# MCU.net
KiCad netlist of a schematic drawn in Altium Designer
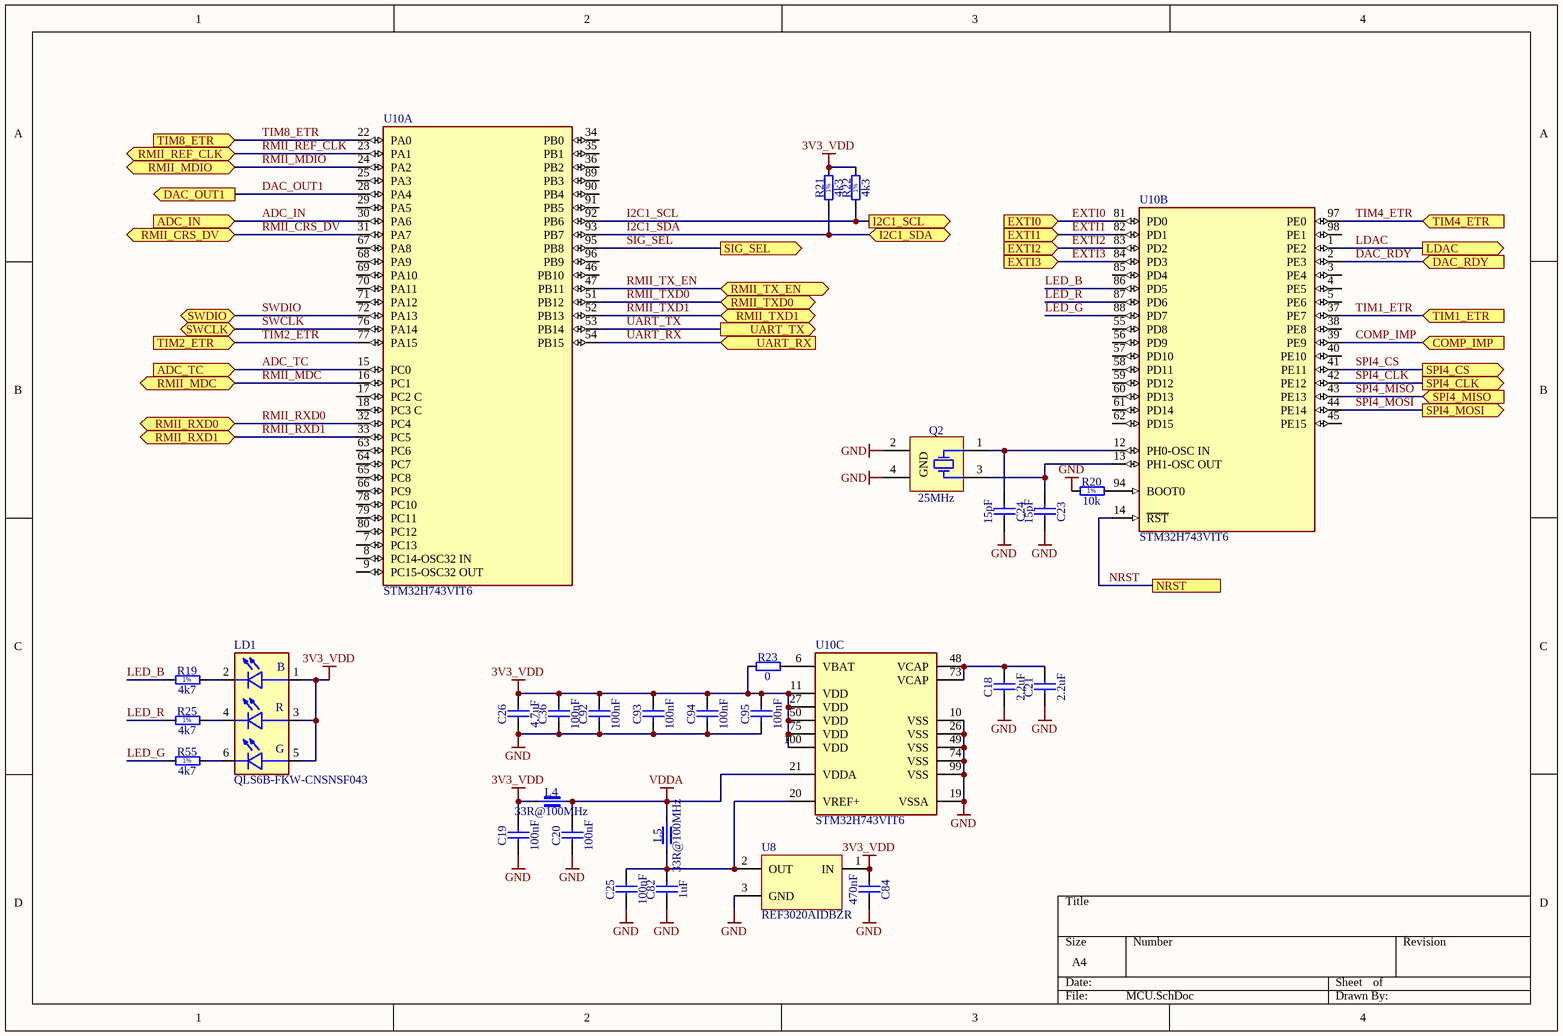
[diagram p0: MCU.SchDoc]

(export (version "E")
  (design (tool "Eeschema 10.0.6"))
  (components
    (comp (ref "C18")
      (value "2.2uF")
      (footprint "CAPC1608X87N")
      (description "Non-polarised capacitor")
      (fields
        (field (name "PART NUMBER") "CC0603_2.2UF_16V_10%_X5R")
        (field (name "VOLTAGE") "16V")
        (field (name "AUTHOR") "CERN DEM JLC")
      )
      (libsource (lib "Capacitors") (part "Capacitor - non polarized"))
    )
    (comp (ref "C19")
      (value "100nF")
      (footprint "CAPC1005X55N")
      (description "Non-polarised capacitor")
      (fields
        (field (name "PART NUMBER") "CC0402_100NF_16V_10%_X7R")
        (field (name "VOLTAGE") "16V")
        (field (name "AUTHOR") "CERN DEM JLC")
      )
      (libsource (lib "Capacitors") (part "Capacitor - non polarized"))
    )
    (comp (ref "C20")
      (value "100nF")
      (footprint "CAPC1005X55N")
      (description "Non-polarised capacitor")
      (fields
        (field (name "PART NUMBER") "CC0402_100NF_16V_10%_X7R")
        (field (name "VOLTAGE") "16V")
        (field (name "AUTHOR") "CERN DEM JLC")
      )
      (libsource (lib "Capacitors") (part "Capacitor - non polarized"))
    )
    (comp (ref "C21")
      (value "2.2uF")
      (footprint "CAPC1608X87N")
      (description "Non-polarised capacitor")
      (fields
        (field (name "PART NUMBER") "CC0603_2.2UF_16V_10%_X5R")
        (field (name "VOLTAGE") "16V")
        (field (name "AUTHOR") "CERN DEM JLC")
      )
      (libsource (lib "Capacitors") (part "Capacitor - non polarized"))
    )
    (comp (ref "C23")
      (value "15pF")
      (footprint "CAPC1005X55N")
      (description "Non-polarised capacitor")
      (fields
        (field (name "PART NUMBER") "CC0402_15PF_50V_5%_C0G")
        (field (name "VOLTAGE") "50V")
        (field (name "AUTHOR") "CERN DEM JLC")
      )
      (libsource (lib "Capacitors") (part "Capacitor - non polarized"))
    )
    (comp (ref "C24")
      (value "15pF")
      (footprint "CAPC1005X55N")
      (description "Non-polarised capacitor")
      (fields
        (field (name "PART NUMBER") "CC0402_15PF_50V_5%_C0G")
        (field (name "VOLTAGE") "50V")
        (field (name "AUTHOR") "CERN DEM JLC")
      )
      (libsource (lib "Capacitors") (part "Capacitor - non polarized"))
    )
    (comp (ref "C25")
      (value "100nF")
      (footprint "CAPC1005X55N")
      (description "Non-polarised capacitor")
      (fields
        (field (name "PART NUMBER") "CC0402_100NF_16V_10%_X7R")
        (field (name "VOLTAGE") "16V")
        (field (name "AUTHOR") "CERN DEM JLC")
      )
      (libsource (lib "Capacitors") (part "Capacitor - non polarized"))
    )
    (comp (ref "C26")
      (value "4.7uF")
      (footprint "CAPC1709X95N")
      (description "Non-polarised capacitor")
      (fields
        (field (name "PART NUMBER") "CC0603_4.7UF_16V_10%_X5R")
        (field (name "VOLTAGE") "16V")
        (field (name "AUTHOR") "CERN DEM JLC")
      )
      (libsource (lib "Capacitors") (part "Capacitor - non polarized"))
    )
    (comp (ref "C36")
      (value "100nF")
      (footprint "CAPC1005X55N")
      (description "Non-polarised capacitor")
      (fields
        (field (name "PART NUMBER") "CC0402_100NF_16V_10%_X7R")
        (field (name "VOLTAGE") "16V")
        (field (name "AUTHOR") "CERN DEM JLC")
      )
      (libsource (lib "Capacitors") (part "Capacitor - non polarized"))
    )
    (comp (ref "C82")
      (value "1uF")
      (footprint "CAPC1005X55N")
      (description "Non-polarised capacitor")
      (fields
        (field (name "PART NUMBER") "CC0402_1UF_16V_10%_X5R")
        (field (name "VOLTAGE") "16V")
        (field (name "AUTHOR") "CERN DEM JLC")
      )
      (libsource (lib "Capacitors") (part "Capacitor - non polarized"))
    )
    (comp (ref "C84")
      (value "470nF")
      (footprint "CAPC1005X55N")
      (description "Non-polarised capacitor")
      (fields
        (field (name "PART NUMBER") "CC0402_470NF_16V_10%_X5R")
        (field (name "VOLTAGE") "16V")
        (field (name "AUTHOR") "CERN DEM JLC")
      )
      (libsource (lib "Capacitors") (part "Capacitor - non polarized"))
    )
    (comp (ref "C92")
      (value "100nF")
      (footprint "CAPC1005X55N")
      (description "Non-polarised capacitor")
      (fields
        (field (name "PART NUMBER") "CC0402_100NF_16V_10%_X7R")
        (field (name "VOLTAGE") "16V")
        (field (name "AUTHOR") "CERN DEM JLC")
      )
      (libsource (lib "Capacitors") (part "Capacitor - non polarized"))
    )
    (comp (ref "C93")
      (value "100nF")
      (footprint "CAPC1005X55N")
      (description "Non-polarised capacitor")
      (fields
        (field (name "PART NUMBER") "CC0402_100NF_16V_10%_X7R")
        (field (name "VOLTAGE") "16V")
        (field (name "AUTHOR") "CERN DEM JLC")
      )
      (libsource (lib "Capacitors") (part "Capacitor - non polarized"))
    )
    (comp (ref "C94")
      (value "100nF")
      (footprint "CAPC1005X55N")
      (description "Non-polarised capacitor")
      (fields
        (field (name "PART NUMBER") "CC0402_100NF_16V_10%_X7R")
        (field (name "VOLTAGE") "16V")
        (field (name "AUTHOR") "CERN DEM JLC")
      )
      (libsource (lib "Capacitors") (part "Capacitor - non polarized"))
    )
    (comp (ref "C95")
      (value "100nF")
      (footprint "CAPC1005X55N")
      (description "Non-polarised capacitor")
      (fields
        (field (name "PART NUMBER") "CC0402_100NF_16V_10%_X7R")
        (field (name "VOLTAGE") "16V")
        (field (name "AUTHOR") "CERN DEM JLC")
      )
      (libsource (lib "Capacitors") (part "Capacitor - non polarized"))
    )
    (comp (ref "L4")
      (value "33R@100MHz")
      (footprint "INDC1005X55N")
      (fields
        (field (name "PART NUMBER") "IND0402_MURATA_BLM15PX330SN1D")
        (field (name "POWER") "3A")
        (field (name "TOLERANCE") "±25%")
        (field (name "AUTHOR") "CERN DEM JMW")
      )
      (libsource (lib "") (part "Ferrite Bead_1"))
    )
    (comp (ref "L5")
      (value "33R@100MHz")
      (footprint "INDC1005X55N")
      (fields
        (field (name "PART NUMBER") "IND0402_MURATA_BLM15PX330SN1D")
        (field (name "POWER") "3A")
        (field (name "TOLERANCE") "±25%")
        (field (name "AUTHOR") "CERN DEM JMW")
      )
      (libsource (lib "Inductors & Transformers") (part "Ferrite Bead"))
    )
    (comp (ref "LD1")
      (value "QLS6B-FKW-CNSNSF043")
      (footprint "LED_QLS6B-FKW-CNSNSF043")
      (fields (field (name "MF") "Cree Inc."))
      (libsource (lib "QLS6B-FKW-CNSNSF043") (part "QLS6B-FKW-CNSNSF043"))
    )
    (comp (ref "Q2")
      (value "25MHz")
      (footprint "XTAL_EPSON_TSX-3225")
      (description "Crystal 4 pins 1=XTAL Control 2=GND3=XTAL 4=GND")
      (fields
        (field (name "PART NUMBER") "XTAL_25MHZ_EPSON_TSX-3225 25.0000MF10Z-AC")
        (field (name "MANUFACTURER") "EPSON")
        (field (name "AUTHOR") "CERN DEM JLC")
      )
      (libsource (lib "ICs And Semiconductors") (part "Quartz Crystal 1X 2GND 3X 4GND"))
    )
    (comp (ref "R19")
      (value "4k7")
      (footprint "RESC1005X40N")
      (description "Resistor - 1%")
      (fields
        (field (name "PART NUMBER") "R0402_4K7_1%_0.0625W_100PPM")
        (field (name "POWER") "0.0625W")
        (field (name "AUTHOR") "CERN DEM JLC")
      )
      (libsource (lib "Resistors") (part "Resistor - 1%"))
    )
    (comp (ref "R20")
      (value "10k")
      (footprint "RESC1005X40N")
      (description "Resistor - 1%")
      (fields
        (field (name "PART NUMBER") "R0402_10K_1%_0.0625W_100PPM")
        (field (name "POWER") "0.0625W")
        (field (name "AUTHOR") "CERN DEM JLC")
      )
      (libsource (lib "Resistors") (part "Resistor - 1%"))
    )
    (comp (ref "R21")
      (value "4k3")
      (footprint "RESC1005X40N")
      (description "Resistor - 1%")
      (fields
        (field (name "PART NUMBER") "R0402_4K3_1%_0.0625W_100PPM")
        (field (name "POWER") "0.0625W")
        (field (name "AUTHOR") "CERN DEM JLC")
      )
      (libsource (lib "Resistors") (part "Resistor - 1%"))
    )
    (comp (ref "R22")
      (value "4k3")
      (footprint "RESC1005X40N")
      (description "Resistor - 1%")
      (fields
        (field (name "PART NUMBER") "R0402_4K3_1%_0.0625W_100PPM")
        (field (name "POWER") "0.0625W")
        (field (name "AUTHOR") "CERN DEM JLC")
      )
      (libsource (lib "Resistors") (part "Resistor - 1%"))
    )
    (comp (ref "R23")
      (value "0")
      (footprint "RESC1005X40N")
      (description "Resistor")
      (fields
        (field (name "PART NUMBER") "R0402_0R_JUMPER")
        (field (name "MANUFACTURER") "GENERIC")
        (field (name "AUTHOR") "CERN DEM JLC")
      )
      (libsource (lib "Resistors") (part "Resistor"))
    )
    (comp (ref "R25")
      (value "4k7")
      (footprint "RESC1005X40N")
      (description "Resistor - 1%")
      (fields
        (field (name "PART NUMBER") "R0402_4K7_1%_0.0625W_100PPM")
        (field (name "POWER") "0.0625W")
        (field (name "AUTHOR") "CERN DEM JLC")
      )
      (libsource (lib "Resistors") (part "Resistor - 1%"))
    )
    (comp (ref "R55")
      (value "4k7")
      (footprint "RESC1005X40N")
      (description "Resistor - 1%")
      (fields
        (field (name "PART NUMBER") "R0402_4K7_1%_0.0625W_100PPM")
        (field (name "POWER") "0.0625W")
        (field (name "AUTHOR") "CERN DEM JLC")
      )
      (libsource (lib "Resistors") (part "Resistor - 1%"))
    )
    (comp (ref "U8")
      (value "REF3020AIDBZR")
      (footprint "DBZ0003A_L")
      (fields (field (name "MANUFACTURER") "Texas Instruments"))
      (libsource (lib "Altium Content Vault") (part "TI-REF3020DBZ3"))
    )
    (comp (ref "U10")
      (value "STM32H743VIT6")
      (footprint "FP-LQFP100-1L-MFG")
      (description "IC MCU 32BIT 2MB FLASH 100LQFP")
      (fields
        (field (name "OCTOPART") "https://octopart.com/stm32h743vit6-stmicroelectronics-76372527")
        (field (name "MANUFACTURER") "STMicroelectronics")
      )
      (libsource (lib "Altium Content Vault") (part "01082ce2885d1d16a22823c45526fe6"))
    )
  )
  (nets
    (net (code "1") (name "/ADC_IN") (class "Default")
      (node (ref "U10") (pin "30") (pinfunction "PA6_30") (pintype "bidirectional"))
    )
    (net (code "2") (name "/ADC_TC") (class "Default")
      (node (ref "U10") (pin "15") (pinfunction "PC0_15") (pintype "bidirectional"))
    )
    (net (code "3") (name "/COMP_IMP") (class "Default")
      (node (ref "U10") (pin "39") (pinfunction "PE9_39") (pintype "bidirectional"))
    )
    (net (code "4") (name "/DAC_OUT1") (class "Default")
      (node (ref "U10") (pin "28") (pinfunction "PA4_28") (pintype "bidirectional"))
    )
    (net (code "5") (name "/DAC_RDY") (class "Default")
      (node (ref "U10") (pin "2") (pinfunction "PE3_2") (pintype "bidirectional"))
    )
    (net (code "6") (name "/EXTI0") (class "Default")
      (node (ref "U10") (pin "81") (pinfunction "PD0_81") (pintype "bidirectional"))
    )
    (net (code "7") (name "/EXTI1") (class "Default")
      (node (ref "U10") (pin "82") (pinfunction "PD1_82") (pintype "bidirectional"))
    )
    (net (code "8") (name "/EXTI2") (class "Default")
      (node (ref "U10") (pin "83") (pinfunction "PD2_83") (pintype "bidirectional"))
    )
    (net (code "9") (name "/EXTI3") (class "Default")
      (node (ref "U10") (pin "84") (pinfunction "PD3_84") (pintype "bidirectional"))
    )
    (net (code "10") (name "/I2C1_SCL") (class "Default")
      (node (ref "R22") (pin "1") (pinfunction "1_1") (pintype "passive"))
      (node (ref "U10") (pin "92") (pinfunction "PB6_92") (pintype "bidirectional"))
    )
    (net (code "11") (name "/I2C1_SDA") (class "Default")
      (node (ref "R21") (pin "1") (pinfunction "1_1") (pintype "passive"))
      (node (ref "U10") (pin "93") (pinfunction "PB7_93") (pintype "bidirectional"))
    )
    (net (code "12") (name "/LDAC") (class "Default")
      (node (ref "U10") (pin "1") (pinfunction "PE2_1") (pintype "bidirectional"))
    )
    (net (code "13") (name "/LED_B") (class "Default")
      (node (ref "R19") (pin "1") (pinfunction "1_1") (pintype "passive"))
      (node (ref "U10") (pin "86") (pinfunction "PD5_86") (pintype "bidirectional"))
    )
    (net (code "14") (name "/LED_G") (class "Default")
      (node (ref "R55") (pin "1") (pinfunction "1_1") (pintype "passive"))
      (node (ref "U10") (pin "88") (pinfunction "PD7_88") (pintype "bidirectional"))
    )
    (net (code "15") (name "/LED_R") (class "Default")
      (node (ref "R25") (pin "1") (pinfunction "1_1") (pintype "passive"))
      (node (ref "U10") (pin "87") (pinfunction "PD6_87") (pintype "bidirectional"))
    )
    (net (code "16") (name "/NRST") (class "Default")
      (node (ref "U10") (pin "14") (pinfunction "~{RST}_14") (pintype "input"))
    )
    (net (code "17") (name "/RMII_CRS_DV") (class "Default")
      (node (ref "U10") (pin "31") (pinfunction "PA7_31") (pintype "bidirectional"))
    )
    (net (code "18") (name "/RMII_MDC") (class "Default")
      (node (ref "U10") (pin "16") (pinfunction "PC1_16") (pintype "bidirectional"))
    )
    (net (code "19") (name "/RMII_MDIO") (class "Default")
      (node (ref "U10") (pin "24") (pinfunction "PA2_24") (pintype "bidirectional"))
    )
    (net (code "20") (name "/RMII_REF_CLK") (class "Default")
      (node (ref "U10") (pin "23") (pinfunction "PA1_23") (pintype "bidirectional"))
    )
    (net (code "21") (name "/RMII_RXD0") (class "Default")
      (node (ref "U10") (pin "32") (pinfunction "PC4_32") (pintype "bidirectional"))
    )
    (net (code "22") (name "/RMII_RXD1") (class "Default")
      (node (ref "U10") (pin "33") (pinfunction "PC5_33") (pintype "bidirectional"))
    )
    (net (code "23") (name "/RMII_TXD0") (class "Default")
      (node (ref "U10") (pin "51") (pinfunction "PB12_51") (pintype "bidirectional"))
    )
    (net (code "24") (name "/RMII_TXD1") (class "Default")
      (node (ref "U10") (pin "52") (pinfunction "PB13_52") (pintype "bidirectional"))
    )
    (net (code "25") (name "/RMII_TX_EN") (class "Default")
      (node (ref "U10") (pin "47") (pinfunction "PB11_47") (pintype "bidirectional"))
    )
    (net (code "26") (name "/SIG_SEL") (class "Default")
      (node (ref "U10") (pin "95") (pinfunction "PB8_95") (pintype "bidirectional"))
    )
    (net (code "27") (name "/SPI4_CLK") (class "Default")
      (node (ref "U10") (pin "42") (pinfunction "PE12_42") (pintype "bidirectional"))
    )
    (net (code "28") (name "/SPI4_CS") (class "Default")
      (node (ref "U10") (pin "41") (pinfunction "PE11_41") (pintype "bidirectional"))
    )
    (net (code "29") (name "/SPI4_MISO") (class "Default")
      (node (ref "U10") (pin "43") (pinfunction "PE13_43") (pintype "bidirectional"))
    )
    (net (code "30") (name "/SPI4_MOSI") (class "Default")
      (node (ref "U10") (pin "44") (pinfunction "PE14_44") (pintype "bidirectional"))
    )
    (net (code "31") (name "/SWCLK") (class "Default")
      (node (ref "U10") (pin "76") (pinfunction "PA14_76") (pintype "bidirectional"))
    )
    (net (code "32") (name "/SWDIO") (class "Default")
      (node (ref "U10") (pin "72") (pinfunction "PA13_72") (pintype "bidirectional"))
    )
    (net (code "33") (name "/TIM1_ETR") (class "Default")
      (node (ref "U10") (pin "37") (pinfunction "PE7_37") (pintype "bidirectional"))
    )
    (net (code "34") (name "/TIM2_ETR") (class "Default")
      (node (ref "U10") (pin "77") (pinfunction "PA15_77") (pintype "bidirectional"))
    )
    (net (code "35") (name "/TIM4_ETR") (class "Default")
      (node (ref "U10") (pin "97") (pinfunction "PE0_97") (pintype "bidirectional"))
    )
    (net (code "36") (name "/TIM8_ETR") (class "Default")
      (node (ref "U10") (pin "22") (pinfunction "PA0_22") (pintype "bidirectional"))
    )
    (net (code "37") (name "/UART_RX") (class "Default")
      (node (ref "U10") (pin "54") (pinfunction "PB15_54") (pintype "bidirectional"))
    )
    (net (code "38") (name "/UART_TX") (class "Default")
      (node (ref "U10") (pin "53") (pinfunction "PB14_53") (pintype "bidirectional"))
    )
    (net (code "39") (name "3V3_VDD") (class "Default")
      (node (ref "C19") (pin "2") (pinfunction "2_2") (pintype "passive"))
      (node (ref "C26") (pin "2") (pinfunction "2_2") (pintype "passive"))
      (node (ref "C36") (pin "2") (pinfunction "2_2") (pintype "passive"))
      (node (ref "C84") (pin "2") (pinfunction "2_2") (pintype "passive"))
      (node (ref "C92") (pin "2") (pinfunction "2_2") (pintype "passive"))
      (node (ref "C93") (pin "2") (pinfunction "2_2") (pintype "passive"))
      (node (ref "C94") (pin "2") (pinfunction "2_2") (pintype "passive"))
      (node (ref "C95") (pin "2") (pinfunction "2_2") (pintype "passive"))
      (node (ref "L4") (pin "1") (pinfunction "1_1") (pintype "passive"))
      (node (ref "LD1") (pin "1") (pinfunction "BLUE_ANODE_1") (pintype "passive"))
      (node (ref "LD1") (pin "3") (pinfunction "RED_ANODE_3") (pintype "passive"))
      (node (ref "LD1") (pin "5") (pinfunction "GREEN_ANODE_5") (pintype "passive"))
      (node (ref "R21") (pin "2") (pinfunction "2_2") (pintype "passive"))
      (node (ref "R22") (pin "2") (pinfunction "2_2") (pintype "passive"))
      (node (ref "R23") (pin "1") (pinfunction "1_1") (pintype "passive"))
      (node (ref "U10") (pin "100") (pinfunction "VDD_100") (pintype "power_in"))
      (node (ref "U10") (pin "11") (pinfunction "VDD_11") (pintype "power_in"))
      (node (ref "U10") (pin "27") (pinfunction "VDD_27") (pintype "power_in"))
      (node (ref "U10") (pin "50") (pinfunction "VDD_50") (pintype "power_in"))
      (node (ref "U10") (pin "75") (pinfunction "VDD_75") (pintype "power_in"))
      (node (ref "U8") (pin "1") (pinfunction "IN_1") (pintype "power_in"))
    )
    (net (code "40") (name "GND") (class "Default")
      (node (ref "C18") (pin "1") (pinfunction "1_1") (pintype "passive"))
      (node (ref "C19") (pin "1") (pinfunction "1_1") (pintype "passive"))
      (node (ref "C20") (pin "1") (pinfunction "1_1") (pintype "passive"))
      (node (ref "C21") (pin "1") (pinfunction "1_1") (pintype "passive"))
      (node (ref "C23") (pin "1") (pinfunction "1_1") (pintype "passive"))
      (node (ref "C24") (pin "1") (pinfunction "1_1") (pintype "passive"))
      (node (ref "C25") (pin "1") (pinfunction "1_1") (pintype "passive"))
      (node (ref "C26") (pin "1") (pinfunction "1_1") (pintype "passive"))
      (node (ref "C36") (pin "1") (pinfunction "1_1") (pintype "passive"))
      (node (ref "C82") (pin "1") (pinfunction "1_1") (pintype "passive"))
      (node (ref "C84") (pin "1") (pinfunction "1_1") (pintype "passive"))
      (node (ref "C92") (pin "1") (pinfunction "1_1") (pintype "passive"))
      (node (ref "C93") (pin "1") (pinfunction "1_1") (pintype "passive"))
      (node (ref "C94") (pin "1") (pinfunction "1_1") (pintype "passive"))
      (node (ref "C95") (pin "1") (pinfunction "1_1") (pintype "passive"))
      (node (ref "Q2") (pin "2") (pinfunction "GND_2") (pintype "power_in"))
      (node (ref "Q2") (pin "4") (pinfunction "GND_4") (pintype "power_in"))
      (node (ref "R20") (pin "1") (pinfunction "1_1") (pintype "passive"))
      (node (ref "U10") (pin "10") (pinfunction "VSS_10") (pintype "power_in"))
      (node (ref "U10") (pin "19") (pinfunction "VSSA_19") (pintype "power_in"))
      (node (ref "U10") (pin "26") (pinfunction "VSS_26") (pintype "power_in"))
      (node (ref "U10") (pin "49") (pinfunction "VSS_49") (pintype "power_in"))
      (node (ref "U10") (pin "74") (pinfunction "VSS_74") (pintype "power_in"))
      (node (ref "U10") (pin "99") (pinfunction "VSS_99") (pintype "power_in"))
      (node (ref "U8") (pin "3") (pinfunction "GND_3") (pintype "power_in"))
    )
    (net (code "41") (name "Net-(C18-Pad2)") (class "Default")
      (node (ref "C18") (pin "2") (pinfunction "2_2") (pintype "passive"))
      (node (ref "C21") (pin "2") (pinfunction "2_2") (pintype "passive"))
      (node (ref "U10") (pin "48") (pinfunction "VCAP_48") (pintype "passive"))
      (node (ref "U10") (pin "73") (pinfunction "VCAP_73") (pintype "passive"))
    )
    (net (code "42") (name "Net-(LD1-BLUE_CATHODE)") (class "Default")
      (node (ref "LD1") (pin "2") (pinfunction "BLUE_CATHODE_2") (pintype "passive"))
      (node (ref "R19") (pin "2") (pinfunction "2_2") (pintype "passive"))
    )
    (net (code "43") (name "Net-(LD1-GREEN_CATHODE)") (class "Default")
      (node (ref "LD1") (pin "6") (pinfunction "GREEN_CATHODE_6") (pintype "passive"))
      (node (ref "R55") (pin "2") (pinfunction "2_2") (pintype "passive"))
    )
    (net (code "44") (name "Net-(LD1-RED_CATHODE)") (class "Default")
      (node (ref "LD1") (pin "4") (pinfunction "RED_CATHODE_4") (pintype "passive"))
      (node (ref "R25") (pin "2") (pinfunction "2_2") (pintype "passive"))
    )
    (net (code "45") (name "Net-(U10B-BOOT0)") (class "Default")
      (node (ref "R20") (pin "2") (pinfunction "2_2") (pintype "passive"))
      (node (ref "U10") (pin "94") (pinfunction "BOOT0_94") (pintype "input"))
    )
    (net (code "46") (name "Net-(U10B-PH0-OSC_IN)") (class "Default")
      (node (ref "C24") (pin "2") (pinfunction "2_2") (pintype "passive"))
      (node (ref "Q2") (pin "1") (pinfunction "X_1") (pintype "passive"))
      (node (ref "U10") (pin "12") (pinfunction "PH0-OSC_IN_12") (pintype "bidirectional"))
    )
    (net (code "47") (name "Net-(U10B-PH1-OSC_OUT)") (class "Default")
      (node (ref "C23") (pin "2") (pinfunction "2_2") (pintype "passive"))
      (node (ref "Q2") (pin "3") (pinfunction "X_3") (pintype "passive"))
      (node (ref "U10") (pin "13") (pinfunction "PH1-OSC_OUT_13") (pintype "bidirectional"))
    )
    (net (code "48") (name "Net-(U10C-VBAT)") (class "Default")
      (node (ref "R23") (pin "2") (pinfunction "2_2") (pintype "passive"))
      (node (ref "U10") (pin "6") (pinfunction "VBAT_6") (pintype "power_in"))
    )
    (net (code "49") (name "Net-(U10C-VREF+)") (class "Default")
      (node (ref "C25") (pin "2") (pinfunction "2_2") (pintype "passive"))
      (node (ref "C82") (pin "2") (pinfunction "2_2") (pintype "passive"))
      (node (ref "L5") (pin "1") (pinfunction "1_1") (pintype "passive"))
      (node (ref "U10") (pin "20") (pinfunction "VREF+_20") (pintype "power_in"))
      (node (ref "U8") (pin "2") (pinfunction "OUT_2") (pintype "power_in"))
    )
    (net (code "50") (name "VDDA") (class "Default")
      (node (ref "C20") (pin "2") (pinfunction "2_2") (pintype "passive"))
      (node (ref "L4") (pin "2") (pinfunction "2_2") (pintype "passive"))
      (node (ref "L5") (pin "2") (pinfunction "2_2") (pintype "passive"))
      (node (ref "U10") (pin "21") (pinfunction "VDDA_21") (pintype "power_in"))
    )
    (net (code "51") (name "unconnected-(U10A-PA3-Pad25)") (class "Default")
      (node (ref "U10") (pin "25") (pinfunction "PA3_25") (pintype "bidirectional"))
    )
    (net (code "52") (name "unconnected-(U10A-PA5-Pad29)") (class "Default")
      (node (ref "U10") (pin "29") (pinfunction "PA5_29") (pintype "bidirectional"))
    )
    (net (code "53") (name "unconnected-(U10A-PA8-Pad67)") (class "Default")
      (node (ref "U10") (pin "67") (pinfunction "PA8_67") (pintype "bidirectional"))
    )
    (net (code "54") (name "unconnected-(U10A-PA9-Pad68)") (class "Default")
      (node (ref "U10") (pin "68") (pinfunction "PA9_68") (pintype "bidirectional"))
    )
    (net (code "55") (name "unconnected-(U10A-PA10-Pad69)") (class "Default")
      (node (ref "U10") (pin "69") (pinfunction "PA10_69") (pintype "bidirectional"))
    )
    (net (code "56") (name "unconnected-(U10A-PA11-Pad70)") (class "Default")
      (node (ref "U10") (pin "70") (pinfunction "PA11_70") (pintype "bidirectional"))
    )
    (net (code "57") (name "unconnected-(U10A-PA12-Pad71)") (class "Default")
      (node (ref "U10") (pin "71") (pinfunction "PA12_71") (pintype "bidirectional"))
    )
    (net (code "58") (name "unconnected-(U10A-PB0-Pad34)") (class "Default")
      (node (ref "U10") (pin "34") (pinfunction "PB0_34") (pintype "bidirectional"))
    )
    (net (code "59") (name "unconnected-(U10A-PB1-Pad35)") (class "Default")
      (node (ref "U10") (pin "35") (pinfunction "PB1_35") (pintype "bidirectional"))
    )
    (net (code "60") (name "unconnected-(U10A-PB2-Pad36)") (class "Default")
      (node (ref "U10") (pin "36") (pinfunction "PB2_36") (pintype "bidirectional"))
    )
    (net (code "61") (name "unconnected-(U10A-PB3-Pad89)") (class "Default")
      (node (ref "U10") (pin "89") (pinfunction "PB3_89") (pintype "bidirectional"))
    )
    (net (code "62") (name "unconnected-(U10A-PB4-Pad90)") (class "Default")
      (node (ref "U10") (pin "90") (pinfunction "PB4_90") (pintype "bidirectional"))
    )
    (net (code "63") (name "unconnected-(U10A-PB5-Pad91)") (class "Default")
      (node (ref "U10") (pin "91") (pinfunction "PB5_91") (pintype "bidirectional"))
    )
    (net (code "64") (name "unconnected-(U10A-PB9-Pad96)") (class "Default")
      (node (ref "U10") (pin "96") (pinfunction "PB9_96") (pintype "bidirectional"))
    )
    (net (code "65") (name "unconnected-(U10A-PB10-Pad46)") (class "Default")
      (node (ref "U10") (pin "46") (pinfunction "PB10_46") (pintype "bidirectional"))
    )
    (net (code "66") (name "unconnected-(U10A-PC2_C-Pad17)") (class "Default")
      (node (ref "U10") (pin "17") (pinfunction "PC2_C_17") (pintype "bidirectional"))
    )
    (net (code "67") (name "unconnected-(U10A-PC3_C-Pad18)") (class "Default")
      (node (ref "U10") (pin "18") (pinfunction "PC3_C_18") (pintype "bidirectional"))
    )
    (net (code "68") (name "unconnected-(U10A-PC6-Pad63)") (class "Default")
      (node (ref "U10") (pin "63") (pinfunction "PC6_63") (pintype "bidirectional"))
    )
    (net (code "69") (name "unconnected-(U10A-PC7-Pad64)") (class "Default")
      (node (ref "U10") (pin "64") (pinfunction "PC7_64") (pintype "bidirectional"))
    )
    (net (code "70") (name "unconnected-(U10A-PC8-Pad65)") (class "Default")
      (node (ref "U10") (pin "65") (pinfunction "PC8_65") (pintype "bidirectional"))
    )
    (net (code "71") (name "unconnected-(U10A-PC9-Pad66)") (class "Default")
      (node (ref "U10") (pin "66") (pinfunction "PC9_66") (pintype "bidirectional"))
    )
    (net (code "72") (name "unconnected-(U10A-PC10-Pad78)") (class "Default")
      (node (ref "U10") (pin "78") (pinfunction "PC10_78") (pintype "bidirectional"))
    )
    (net (code "73") (name "unconnected-(U10A-PC11-Pad79)") (class "Default")
      (node (ref "U10") (pin "79") (pinfunction "PC11_79") (pintype "bidirectional"))
    )
    (net (code "74") (name "unconnected-(U10A-PC12-Pad80)") (class "Default")
      (node (ref "U10") (pin "80") (pinfunction "PC12_80") (pintype "bidirectional"))
    )
    (net (code "75") (name "unconnected-(U10A-PC13-Pad7)") (class "Default")
      (node (ref "U10") (pin "7") (pinfunction "PC13_7") (pintype "bidirectional"))
    )
    (net (code "76") (name "unconnected-(U10A-PC14-OSC32_IN-Pad8)") (class "Default")
      (node (ref "U10") (pin "8") (pinfunction "PC14-OSC32_IN_8") (pintype "bidirectional"))
    )
    (net (code "77") (name "unconnected-(U10A-PC15-OSC32_OUT-Pad9)") (class "Default")
      (node (ref "U10") (pin "9") (pinfunction "PC15-OSC32_OUT_9") (pintype "bidirectional"))
    )
    (net (code "78") (name "unconnected-(U10B-PD4-Pad85)") (class "Default")
      (node (ref "U10") (pin "85") (pinfunction "PD4_85") (pintype "bidirectional"))
    )
    (net (code "79") (name "unconnected-(U10B-PD8-Pad55)") (class "Default")
      (node (ref "U10") (pin "55") (pinfunction "PD8_55") (pintype "bidirectional"))
    )
    (net (code "80") (name "unconnected-(U10B-PD9-Pad56)") (class "Default")
      (node (ref "U10") (pin "56") (pinfunction "PD9_56") (pintype "bidirectional"))
    )
    (net (code "81") (name "unconnected-(U10B-PD10-Pad57)") (class "Default")
      (node (ref "U10") (pin "57") (pinfunction "PD10_57") (pintype "bidirectional"))
    )
    (net (code "82") (name "unconnected-(U10B-PD11-Pad58)") (class "Default")
      (node (ref "U10") (pin "58") (pinfunction "PD11_58") (pintype "bidirectional"))
    )
    (net (code "83") (name "unconnected-(U10B-PD12-Pad59)") (class "Default")
      (node (ref "U10") (pin "59") (pinfunction "PD12_59") (pintype "bidirectional"))
    )
    (net (code "84") (name "unconnected-(U10B-PD13-Pad60)") (class "Default")
      (node (ref "U10") (pin "60") (pinfunction "PD13_60") (pintype "bidirectional"))
    )
    (net (code "85") (name "unconnected-(U10B-PD14-Pad61)") (class "Default")
      (node (ref "U10") (pin "61") (pinfunction "PD14_61") (pintype "bidirectional"))
    )
    (net (code "86") (name "unconnected-(U10B-PD15-Pad62)") (class "Default")
      (node (ref "U10") (pin "62") (pinfunction "PD15_62") (pintype "bidirectional"))
    )
    (net (code "87") (name "unconnected-(U10B-PE1-Pad98)") (class "Default")
      (node (ref "U10") (pin "98") (pinfunction "PE1_98") (pintype "bidirectional"))
    )
    (net (code "88") (name "unconnected-(U10B-PE4-Pad3)") (class "Default")
      (node (ref "U10") (pin "3") (pinfunction "PE4_3") (pintype "bidirectional"))
    )
    (net (code "89") (name "unconnected-(U10B-PE5-Pad4)") (class "Default")
      (node (ref "U10") (pin "4") (pinfunction "PE5_4") (pintype "bidirectional"))
    )
    (net (code "90") (name "unconnected-(U10B-PE6-Pad5)") (class "Default")
      (node (ref "U10") (pin "5") (pinfunction "PE6_5") (pintype "bidirectional"))
    )
    (net (code "91") (name "unconnected-(U10B-PE8-Pad38)") (class "Default")
      (node (ref "U10") (pin "38") (pinfunction "PE8_38") (pintype "bidirectional"))
    )
    (net (code "92") (name "unconnected-(U10B-PE10-Pad40)") (class "Default")
      (node (ref "U10") (pin "40") (pinfunction "PE10_40") (pintype "bidirectional"))
    )
    (net (code "93") (name "unconnected-(U10B-PE15-Pad45)") (class "Default")
      (node (ref "U10") (pin "45") (pinfunction "PE15_45") (pintype "bidirectional"))
    )
  )
)
